# tooth.net
KiCad netlist of a schematic drawn in EAGLE
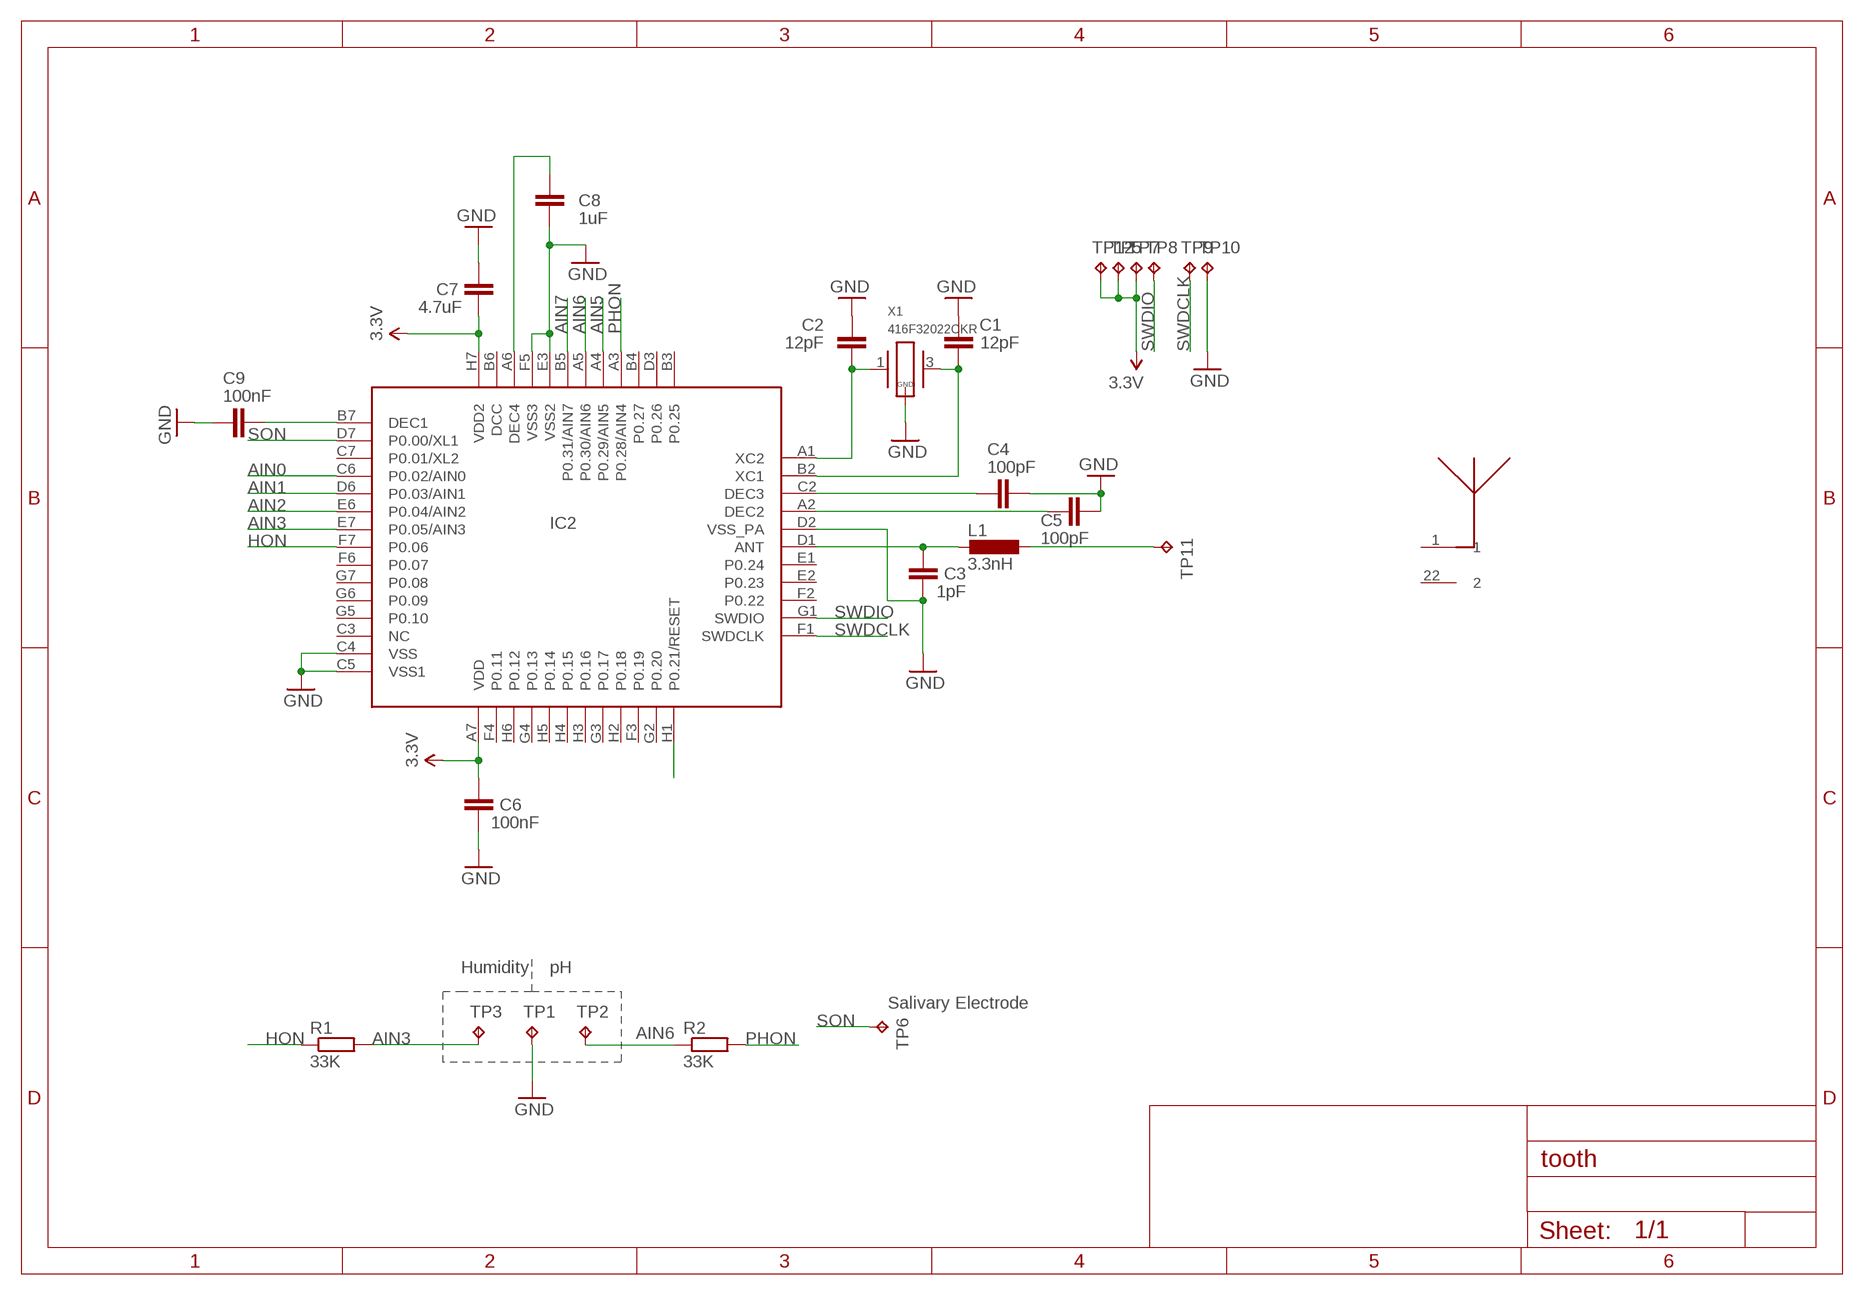
[diagram p0: schematic, sheet 1]

(export (version "E")
  (design (tool "Eeschema 10.0.6"))
  (components
    (comp (ref "C1")
      (value "12pF")
      (footprint "eagle-import:C0201")
      (libsource (lib "eagle-import") (part "C-EUC0201"))
    )
    (comp (ref "C2")
      (value "12pF")
      (footprint "eagle-import:C0201")
      (libsource (lib "eagle-import") (part "C-EUC0201"))
    )
    (comp (ref "C3")
      (value "1pF")
      (footprint "eagle-import:C0201")
      (libsource (lib "eagle-import") (part "C-EUC0201"))
    )
    (comp (ref "C4")
      (value "100pF")
      (footprint "eagle-import:C0201")
      (libsource (lib "eagle-import") (part "C-EUC0201"))
    )
    (comp (ref "C5")
      (value "100pF")
      (footprint "eagle-import:C0201")
      (libsource (lib "eagle-import") (part "C-EUC0201"))
    )
    (comp (ref "C6")
      (value "100nF")
      (footprint "eagle-import:C0201")
      (libsource (lib "eagle-import") (part "C-EUC0201"))
    )
    (comp (ref "C7")
      (value "4.7uF")
      (footprint "eagle-import:C0402")
      (libsource (lib "eagle-import") (part "C-EUC0402"))
    )
    (comp (ref "C8")
      (value "1uF")
      (footprint "eagle-import:C0402")
      (libsource (lib "eagle-import") (part "C-EUC0402"))
    )
    (comp (ref "C9")
      (value "100nF")
      (footprint "eagle-import:C0201")
      (libsource (lib "eagle-import") (part "C-EUC0201"))
    )
    (comp (ref "IC2")
      (value "NRF52832")
      (footprint "eagle-import:NRF52832_WLCSP")
      (libsource (lib "eagle-import") (part "NRF52832"))
    )
    (comp (ref "L1")
      (value "3.3nH")
      (footprint "eagle-import:L0201")
      (libsource (lib "eagle-import") (part "L-EUL0201"))
    )
    (comp (ref "R1")
      (value "33K")
      (footprint "eagle-import:R0201")
      (libsource (lib "eagle-import") (part "R-EU_R0201"))
    )
    (comp (ref "R2")
      (value "33K")
      (footprint "eagle-import:R0201")
      (libsource (lib "eagle-import") (part "R-EU_R0201"))
    )
    (comp (ref "TP1")
      (value "TPTP10R")
      (footprint "eagle-import:TP10R")
      (libsource (lib "eagle-import") (part "TPTP10R"))
    )
    (comp (ref "TP2")
      (value "TPTP10R")
      (footprint "eagle-import:TP10R")
      (libsource (lib "eagle-import") (part "TPTP10R"))
    )
    (comp (ref "TP3")
      (value "TPTP10R")
      (footprint "eagle-import:TP10R")
      (libsource (lib "eagle-import") (part "TPTP10R"))
    )
    (comp (ref "TP5")
      (value "TPTP15R")
      (footprint "eagle-import:TP15R")
      (libsource (lib "eagle-import") (part "TPTP15R"))
    )
    (comp (ref "TP6")
      (value "TPTP15R")
      (footprint "eagle-import:TP15R")
      (libsource (lib "eagle-import") (part "TPTP15R"))
    )
    (comp (ref "TP7")
      (value "TPTP15R")
      (footprint "eagle-import:TP15R")
      (libsource (lib "eagle-import") (part "TPTP15R"))
    )
    (comp (ref "TP8")
      (value "TPTP15R")
      (footprint "eagle-import:TP15R")
      (libsource (lib "eagle-import") (part "TPTP15R"))
    )
    (comp (ref "TP9")
      (value "TPTP15R")
      (footprint "eagle-import:TP15R")
      (libsource (lib "eagle-import") (part "TPTP15R"))
    )
    (comp (ref "TP10")
      (value "TPTP15R")
      (footprint "eagle-import:TP15R")
      (libsource (lib "eagle-import") (part "TPTP15R"))
    )
    (comp (ref "TP11")
      (value "TPTP10R")
      (footprint "eagle-import:TP10R")
      (libsource (lib "eagle-import") (part "TPTP10R"))
    )
    (comp (ref "TP12")
      (value "TPTP15R")
      (footprint "eagle-import:TP15R")
      (libsource (lib "eagle-import") (part "TPTP15R"))
    )
    (comp (ref "U$1")
      (value "ACA-102-T")
      (footprint "eagle-import:ACA-102-T")
      (libsource (lib "eagle-import") (part "ACA-102-T"))
    )
    (comp (ref "X1")
      (value "416F32022CKR")
      (footprint "eagle-import:M416")
      (libsource (lib "eagle-import") (part "M416F26022CKR"))
    )
  )
  (nets
    (net (code "1") (name "/AIN0") (class "Default")
      (node (ref "IC2") (pin "C6") (pinfunction "P0.02/AIN0_C6") (pintype "bidirectional"))
    )
    (net (code "2") (name "/AIN1") (class "Default")
      (node (ref "IC2") (pin "D6") (pinfunction "P0.03/AIN1_D6") (pintype "bidirectional"))
    )
    (net (code "3") (name "/AIN2") (class "Default")
      (node (ref "IC2") (pin "E6") (pinfunction "P0.04/AIN2_E6") (pintype "bidirectional"))
    )
    (net (code "4") (name "/AIN3") (class "Default")
      (node (ref "IC2") (pin "E7") (pinfunction "P0.05/AIN3_E7") (pintype "bidirectional"))
      (node (ref "R1") (pin "2") (pinfunction "2_2") (pintype "passive"))
      (node (ref "TP3") (pin "TP") (pinfunction "TP_TP") (pintype "input"))
    )
    (net (code "5") (name "/AIN5") (class "Default")
      (node (ref "IC2") (pin "A4") (pinfunction "P0.29/AIN5_A4") (pintype "bidirectional"))
    )
    (net (code "6") (name "/AIN6") (class "Default")
      (node (ref "IC2") (pin "A5") (pinfunction "P0.30/AIN6_A5") (pintype "bidirectional"))
      (node (ref "R2") (pin "1") (pinfunction "1_1") (pintype "passive"))
      (node (ref "TP2") (pin "TP") (pinfunction "TP_TP") (pintype "input"))
    )
    (net (code "7") (name "/AIN7") (class "Default")
      (node (ref "IC2") (pin "B5") (pinfunction "P0.31/AIN7_B5") (pintype "bidirectional"))
    )
    (net (code "8") (name "/HON") (class "Default")
      (node (ref "IC2") (pin "F7") (pinfunction "P0.06_F7") (pintype "bidirectional"))
      (node (ref "R1") (pin "1") (pinfunction "1_1") (pintype "passive"))
    )
    (net (code "9") (name "/PHON") (class "Default")
      (node (ref "IC2") (pin "A3") (pinfunction "P0.28/AIN4_A3") (pintype "bidirectional"))
      (node (ref "R2") (pin "2") (pinfunction "2_2") (pintype "passive"))
    )
    (net (code "10") (name "/SON") (class "Default")
      (node (ref "IC2") (pin "D7") (pinfunction "P0.00/XL1_D7") (pintype "bidirectional"))
      (node (ref "TP6") (pin "TP") (pinfunction "TP_TP") (pintype "input"))
    )
    (net (code "11") (name "/SWDCLK") (class "Default")
      (node (ref "IC2") (pin "F1") (pinfunction "SWDCLK_F1") (pintype "bidirectional"))
      (node (ref "TP9") (pin "TP") (pinfunction "TP_TP") (pintype "input"))
    )
    (net (code "12") (name "/SWDIO") (class "Default")
      (node (ref "IC2") (pin "G1") (pinfunction "SWDIO_G1") (pintype "bidirectional"))
      (node (ref "TP8") (pin "TP") (pinfunction "TP_TP") (pintype "input"))
    )
    (net (code "13") (name "3.3V") (class "Default")
      (node (ref "C6") (pin "2") (pinfunction "2_2") (pintype "passive"))
      (node (ref "C7") (pin "2") (pinfunction "2_2") (pintype "passive"))
      (node (ref "IC2") (pin "A7") (pinfunction "VDD_A7") (pintype "bidirectional"))
      (node (ref "IC2") (pin "H7") (pinfunction "VDD2_H7") (pintype "bidirectional"))
      (node (ref "TP12") (pin "TP") (pinfunction "TP_TP") (pintype "input"))
      (node (ref "TP5") (pin "TP") (pinfunction "TP_TP") (pintype "input"))
      (node (ref "TP7") (pin "TP") (pinfunction "TP_TP") (pintype "input"))
    )
    (net (code "14") (name "GND") (class "Default")
      (node (ref "C1") (pin "1") (pinfunction "1_1") (pintype "passive"))
      (node (ref "C2") (pin "1") (pinfunction "1_1") (pintype "passive"))
      (node (ref "C3") (pin "2") (pinfunction "2_2") (pintype "passive"))
      (node (ref "C4") (pin "2") (pinfunction "2_2") (pintype "passive"))
      (node (ref "C5") (pin "2") (pinfunction "2_2") (pintype "passive"))
      (node (ref "C6") (pin "1") (pinfunction "1_1") (pintype "passive"))
      (node (ref "C7") (pin "1") (pinfunction "1_1") (pintype "passive"))
      (node (ref "C8") (pin "2") (pinfunction "2_2") (pintype "passive"))
      (node (ref "C9") (pin "2") (pinfunction "2_2") (pintype "passive"))
      (node (ref "IC2") (pin "C4") (pinfunction "VSS_C4") (pintype "bidirectional"))
      (node (ref "IC2") (pin "C5") (pinfunction "VSS1_C5") (pintype "bidirectional"))
      (node (ref "IC2") (pin "D2") (pinfunction "VSS_PA_D2") (pintype "bidirectional"))
      (node (ref "IC2") (pin "E3") (pinfunction "VSS2_E3") (pintype "bidirectional"))
      (node (ref "IC2") (pin "F5") (pinfunction "VSS3_F5") (pintype "bidirectional"))
      (node (ref "TP1") (pin "TP") (pinfunction "TP_TP") (pintype "input"))
      (node (ref "TP10") (pin "TP") (pinfunction "TP_TP") (pintype "input"))
      (node (ref "X1") (pin "2") (pinfunction "GND_2") (pintype "bidirectional"))
      (node (ref "X1") (pin "4") (pinfunction "GND_4") (pintype "bidirectional"))
    )
    (net (code "15") (name "Net-(IC2-ANT)") (class "Default")
      (node (ref "C3") (pin "1") (pinfunction "1_1") (pintype "passive"))
      (node (ref "IC2") (pin "D1") (pinfunction "ANT_D1") (pintype "bidirectional"))
      (node (ref "L1") (pin "2") (pinfunction "2_2") (pintype "passive"))
    )
    (net (code "16") (name "Net-(IC2-DEC1)") (class "Default")
      (node (ref "C9") (pin "1") (pinfunction "1_1") (pintype "passive"))
      (node (ref "IC2") (pin "B7") (pinfunction "DEC1_B7") (pintype "bidirectional"))
    )
    (net (code "17") (name "Net-(IC2-DEC2)") (class "Default")
      (node (ref "C5") (pin "1") (pinfunction "1_1") (pintype "passive"))
      (node (ref "IC2") (pin "A2") (pinfunction "DEC2_A2") (pintype "bidirectional"))
    )
    (net (code "18") (name "Net-(IC2-DEC3)") (class "Default")
      (node (ref "C4") (pin "1") (pinfunction "1_1") (pintype "passive"))
      (node (ref "IC2") (pin "C2") (pinfunction "DEC3_C2") (pintype "bidirectional"))
    )
    (net (code "19") (name "Net-(IC2-DEC4)") (class "Default")
      (node (ref "C8") (pin "1") (pinfunction "1_1") (pintype "passive"))
      (node (ref "IC2") (pin "A6") (pinfunction "DEC4_A6") (pintype "bidirectional"))
    )
    (net (code "20") (name "Net-(IC2-XC1)") (class "Default")
      (node (ref "C1") (pin "2") (pinfunction "2_2") (pintype "passive"))
      (node (ref "IC2") (pin "B2") (pinfunction "XC1_B2") (pintype "bidirectional"))
      (node (ref "X1") (pin "3") (pinfunction "2_3") (pintype "bidirectional"))
    )
    (net (code "21") (name "Net-(IC2-XC2)") (class "Default")
      (node (ref "C2") (pin "2") (pinfunction "2_2") (pintype "passive"))
      (node (ref "IC2") (pin "A1") (pinfunction "XC2_A1") (pintype "bidirectional"))
      (node (ref "X1") (pin "1") (pinfunction "1_1") (pintype "bidirectional"))
    )
    (net (code "22") (name "Net-(L1-Pad1)") (class "Default")
      (node (ref "L1") (pin "1") (pinfunction "1_1") (pintype "passive"))
      (node (ref "TP11") (pin "TP") (pinfunction "TP_TP") (pintype "input"))
    )
    (net (code "23") (name "unconnected-(IC2-DCC-PadB6)") (class "Default")
      (node (ref "IC2") (pin "B6") (pinfunction "DCC_B6") (pintype "bidirectional"))
    )
    (net (code "24") (name "unconnected-(IC2-NC-PadC3)") (class "Default")
      (node (ref "IC2") (pin "C3") (pinfunction "NC_C3") (pintype "bidirectional"))
    )
    (net (code "25") (name "unconnected-(IC2-P0.01{slash}XL2-PadC7)") (class "Default")
      (node (ref "IC2") (pin "C7") (pinfunction "P0.01/XL2_C7") (pintype "bidirectional"))
    )
    (net (code "26") (name "unconnected-(IC2-P0.07-PadF6)") (class "Default")
      (node (ref "IC2") (pin "F6") (pinfunction "P0.07_F6") (pintype "bidirectional"))
    )
    (net (code "27") (name "unconnected-(IC2-P0.08-PadG7)") (class "Default")
      (node (ref "IC2") (pin "G7") (pinfunction "P0.08_G7") (pintype "bidirectional"))
    )
    (net (code "28") (name "unconnected-(IC2-P0.09-PadG6)") (class "Default")
      (node (ref "IC2") (pin "G6") (pinfunction "P0.09_G6") (pintype "bidirectional"))
    )
    (net (code "29") (name "unconnected-(IC2-P0.10-PadG5)") (class "Default")
      (node (ref "IC2") (pin "G5") (pinfunction "P0.10_G5") (pintype "bidirectional"))
    )
    (net (code "30") (name "unconnected-(IC2-P0.11-PadF4)") (class "Default")
      (node (ref "IC2") (pin "F4") (pinfunction "P0.11_F4") (pintype "bidirectional"))
    )
    (net (code "31") (name "unconnected-(IC2-P0.12-PadH6)") (class "Default")
      (node (ref "IC2") (pin "H6") (pinfunction "P0.12_H6") (pintype "bidirectional"))
    )
    (net (code "32") (name "unconnected-(IC2-P0.13-PadG4)") (class "Default")
      (node (ref "IC2") (pin "G4") (pinfunction "P0.13_G4") (pintype "bidirectional"))
    )
    (net (code "33") (name "unconnected-(IC2-P0.14-PadH5)") (class "Default")
      (node (ref "IC2") (pin "H5") (pinfunction "P0.14_H5") (pintype "bidirectional"))
    )
    (net (code "34") (name "unconnected-(IC2-P0.15-PadH4)") (class "Default")
      (node (ref "IC2") (pin "H4") (pinfunction "P0.15_H4") (pintype "bidirectional"))
    )
    (net (code "35") (name "unconnected-(IC2-P0.16-PadH3)") (class "Default")
      (node (ref "IC2") (pin "H3") (pinfunction "P0.16_H3") (pintype "bidirectional"))
    )
    (net (code "36") (name "unconnected-(IC2-P0.17-PadG3)") (class "Default")
      (node (ref "IC2") (pin "G3") (pinfunction "P0.17_G3") (pintype "bidirectional"))
    )
    (net (code "37") (name "unconnected-(IC2-P0.18-PadH2)") (class "Default")
      (node (ref "IC2") (pin "H2") (pinfunction "P0.18_H2") (pintype "bidirectional"))
    )
    (net (code "38") (name "unconnected-(IC2-P0.19-PadF3)") (class "Default")
      (node (ref "IC2") (pin "F3") (pinfunction "P0.19_F3") (pintype "bidirectional"))
    )
    (net (code "39") (name "unconnected-(IC2-P0.20-PadG2)") (class "Default")
      (node (ref "IC2") (pin "G2") (pinfunction "P0.20_G2") (pintype "bidirectional"))
    )
    (net (code "40") (name "unconnected-(IC2-P0.21{slash}RESET-PadH1)") (class "Default")
      (node (ref "IC2") (pin "H1") (pinfunction "P0.21/RESET_H1") (pintype "bidirectional"))
    )
    (net (code "41") (name "unconnected-(IC2-P0.22-PadF2)") (class "Default")
      (node (ref "IC2") (pin "F2") (pinfunction "P0.22_F2") (pintype "bidirectional"))
    )
    (net (code "42") (name "unconnected-(IC2-P0.23-PadE2)") (class "Default")
      (node (ref "IC2") (pin "E2") (pinfunction "P0.23_E2") (pintype "bidirectional"))
    )
    (net (code "43") (name "unconnected-(IC2-P0.24-PadE1)") (class "Default")
      (node (ref "IC2") (pin "E1") (pinfunction "P0.24_E1") (pintype "bidirectional"))
    )
    (net (code "44") (name "unconnected-(IC2-P0.25-PadB3)") (class "Default")
      (node (ref "IC2") (pin "B3") (pinfunction "P0.25_B3") (pintype "bidirectional"))
    )
    (net (code "45") (name "unconnected-(IC2-P0.26-PadD3)") (class "Default")
      (node (ref "IC2") (pin "D3") (pinfunction "P0.26_D3") (pintype "bidirectional"))
    )
    (net (code "46") (name "unconnected-(IC2-P0.27-PadB4)") (class "Default")
      (node (ref "IC2") (pin "B4") (pinfunction "P0.27_B4") (pintype "bidirectional"))
    )
    (net (code "47") (name "unconnected-(U$1-2-Pad22)") (class "Default")
      (node (ref "U$1") (pin "22") (pinfunction "2_22") (pintype "bidirectional"))
    )
    (net (code "48") (name "unconnected-(U$1-Pad1)") (class "Default")
      (node (ref "U$1") (pin "1") (pinfunction "1_1") (pintype "bidirectional"))
    )
  )
)
